# Philip_Neill_Schaltung.net
KiCad netlist of a schematic drawn in EAGLE
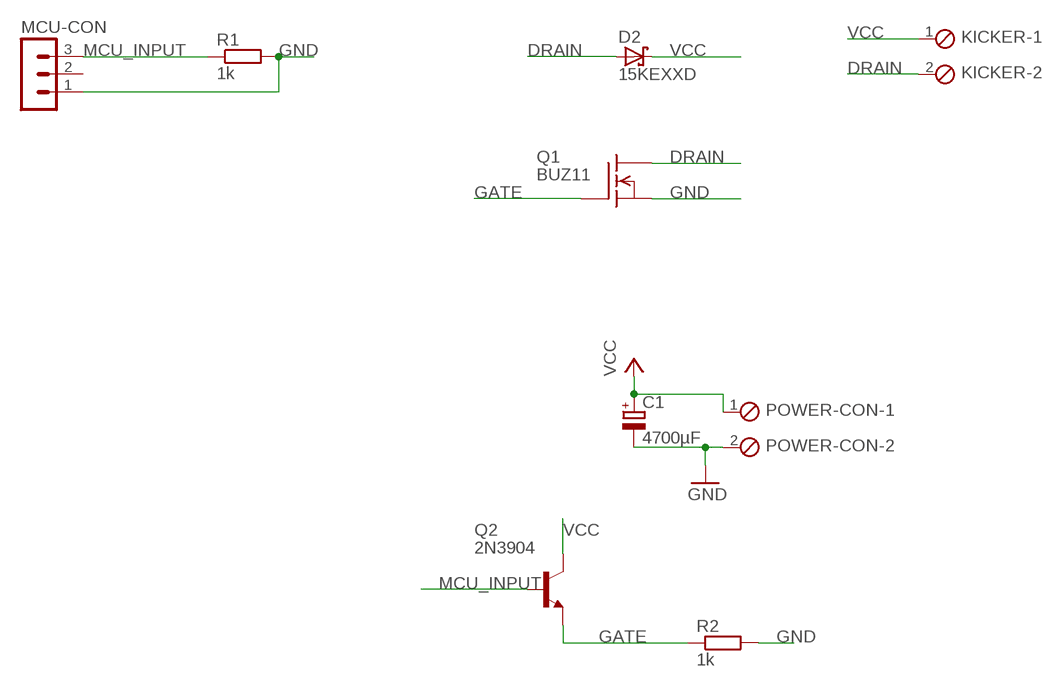
[diagram p0: schematic, sheet 1]

(export (version "E")
  (design (tool "Eeschema 10.0.6"))
  (components
    (comp (ref "C1")
      (value "4700µF")
      (footprint "eagle-import:EB20D")
      (libsource (lib "eagle-import") (part "CPOL-EUE10-20"))
    )
    (comp (ref "D2")
      (value "15KEXXD")
      (footprint "eagle-import:DO201T15")
      (libsource (lib "eagle-import") (part "15KEXXD"))
    )
    (comp (ref "KICKER")
      (value "MPT2")
      (footprint "eagle-import:2POL254")
      (libsource (lib "eagle-import") (part "MPT2"))
    )
    (comp (ref "MCU-CON")
      (value "MA03-1")
      (footprint "eagle-import:MA03-1")
      (libsource (lib "eagle-import") (part "MA03-1"))
    )
    (comp (ref "POWER-CON")
      (value "MPT2")
      (footprint "eagle-import:2POL254")
      (libsource (lib "eagle-import") (part "MPT2"))
    )
    (comp (ref "Q1")
      (value "BUZ11")
      (footprint "eagle-import:TO220")
      (libsource (lib "eagle-import") (part "BUZ11"))
    )
    (comp (ref "Q2")
      (value "2N3904")
      (footprint "eagle-import:TO92")
      (libsource (lib "eagle-import") (part "2N3904"))
    )
    (comp (ref "R1")
      (value "1k")
      (footprint "eagle-import:0207_7")
      (libsource (lib "eagle-import") (part "R-EU_0207/7"))
    )
    (comp (ref "R2")
      (value "1k")
      (footprint "eagle-import:0207_7")
      (libsource (lib "eagle-import") (part "R-EU_0207/7"))
    )
  )
  (nets
    (net (code "1") (name "/DRAIN") (class "Default")
      (node (ref "D2") (pin "A") (pinfunction "A_A") (pintype "passive"))
      (node (ref "KICKER") (pin "2") (pinfunction "1_2") (pintype "passive"))
      (node (ref "Q1") (pin "2") (pinfunction "D_2") (pintype "passive"))
    )
    (net (code "2") (name "/GATE") (class "Default")
      (node (ref "Q1") (pin "1") (pinfunction "G_1") (pintype "passive"))
      (node (ref "Q2") (pin "3") (pinfunction "E_3") (pintype "passive"))
      (node (ref "R2") (pin "1") (pinfunction "1_1") (pintype "passive"))
    )
    (net (code "3") (name "/MCU_INPUT") (class "Default")
      (node (ref "MCU-CON") (pin "3") (pinfunction "3_3") (pintype "passive"))
      (node (ref "Q2") (pin "2") (pinfunction "B_2") (pintype "passive"))
      (node (ref "R1") (pin "1") (pinfunction "1_1") (pintype "passive"))
    )
    (net (code "4") (name "GND") (class "Default")
      (node (ref "C1") (pin "-") (pinfunction "-_-") (pintype "passive"))
      (node (ref "MCU-CON") (pin "1") (pinfunction "1_1") (pintype "passive"))
      (node (ref "POWER-CON") (pin "2") (pinfunction "1_2") (pintype "passive"))
      (node (ref "Q1") (pin "3") (pinfunction "S_3") (pintype "passive"))
      (node (ref "R1") (pin "2") (pinfunction "2_2") (pintype "passive"))
      (node (ref "R2") (pin "2") (pinfunction "2_2") (pintype "passive"))
    )
    (net (code "5") (name "VCC") (class "Default")
      (node (ref "C1") (pin "+") (pinfunction "+_+") (pintype "passive"))
      (node (ref "D2") (pin "C") (pinfunction "C_C") (pintype "passive"))
      (node (ref "KICKER") (pin "1") (pinfunction "1_1") (pintype "passive"))
      (node (ref "POWER-CON") (pin "1") (pinfunction "1_1") (pintype "passive"))
      (node (ref "Q2") (pin "1") (pinfunction "C_1") (pintype "passive"))
    )
    (net (code "6") (name "unconnected-(MCU-CON-Pad2)") (class "Default")
      (node (ref "MCU-CON") (pin "2") (pinfunction "2_2") (pintype "passive"))
    )
  )
)
